# Schematic.net
KiCad netlist of a schematic drawn in Altium Designer
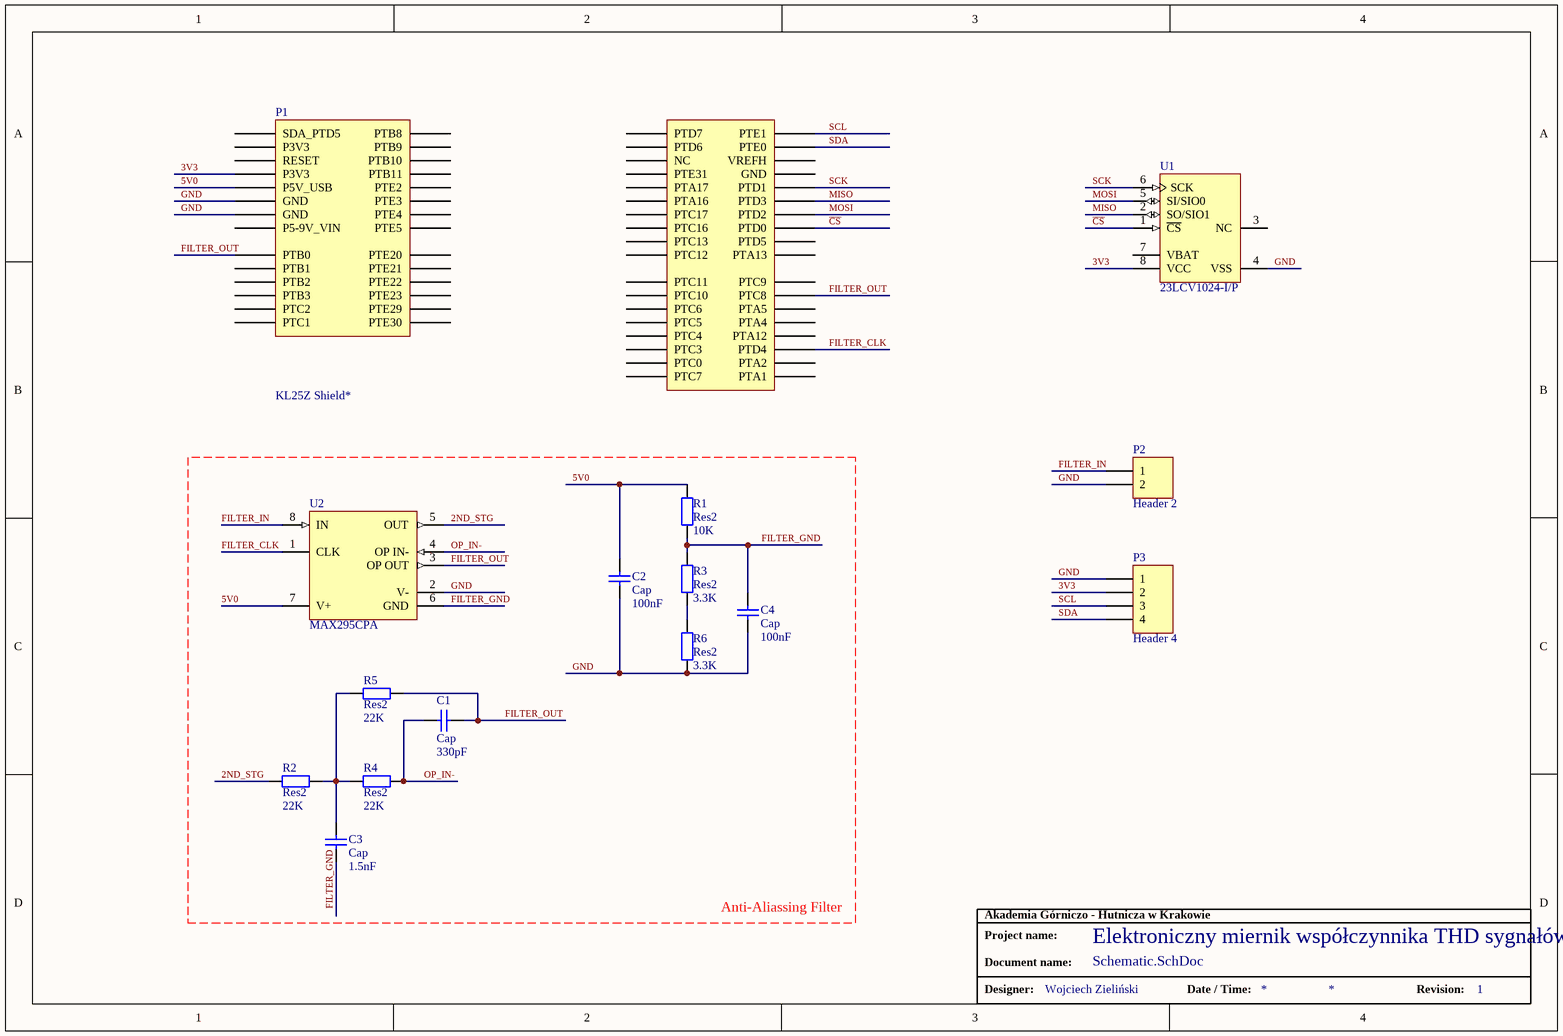
[diagram p0: Schematic.SchDoc]

(export (version "E")
  (design (tool "Eeschema 10.0.6"))
  (components
    (comp (ref "C1")
      (value "Cap")
      (footprint "RAD-0.1")
      (description "Capacitor")
      (fields (field (name "ALTIUM_VALUE") "330pF") (field (name "PUBLISHER") "Altium Limited"))
      (libsource (lib "Miscellaneous Devices") (part "Cap"))
    )
    (comp (ref "C2")
      (value "Cap")
      (footprint "RAD-0.1")
      (description "Capacitor")
      (fields (field (name "ALTIUM_VALUE") "100nF") (field (name "PUBLISHER") "Altium Limited"))
      (libsource (lib "Miscellaneous Devices") (part "Cap"))
    )
    (comp (ref "C3")
      (value "Cap")
      (footprint "RAD-0.1")
      (description "Capacitor")
      (fields (field (name "ALTIUM_VALUE") "1.5nF") (field (name "PUBLISHER") "Altium Limited"))
      (libsource (lib "Miscellaneous Devices") (part "Cap"))
    )
    (comp (ref "C4")
      (value "Cap")
      (footprint "RAD-0.1")
      (description "Capacitor")
      (fields (field (name "ALTIUM_VALUE") "100nF") (field (name "PUBLISHER") "Altium Limited"))
      (libsource (lib "Miscellaneous Devices") (part "Cap"))
    )
    (comp (ref "P1")
      (value "KL25Z Shield*")
      (footprint "Freedom KL25Z Headerarray")
      (description "FRDM KL25Z Shield")
      (libsource (lib "FreedomKL25Z") (part "Freedom KL25Z Header"))
    )
    (comp (ref "P2")
      (value "Header 2")
      (footprint "HDR1X2")
      (description "Header, 2-Pin")
      (fields (field (name "PUBLISHER") "Altium Limited"))
      (libsource (lib "Miscellaneous Connectors") (part "Header 2"))
    )
    (comp (ref "P3")
      (value "Header 4")
      (footprint "HDR1X4")
      (description "Header, 4-Pin")
      (fields (field (name "PUBLISHER") "Altium Limited"))
      (libsource (lib "Miscellaneous Connectors") (part "Header 4"))
    )
    (comp (ref "R1")
      (value "Res2")
      (footprint "AXIAL-0.4")
      (description "Resistor")
      (fields (field (name "ALTIUM_VALUE") "10K") (field (name "PUBLISHER") "Altium Limited"))
      (libsource (lib "Miscellaneous Devices") (part "Res2"))
    )
    (comp (ref "R2")
      (value "Res2")
      (footprint "AXIAL-0.4")
      (description "Resistor")
      (fields (field (name "ALTIUM_VALUE") "22K") (field (name "PUBLISHER") "Altium Limited"))
      (libsource (lib "") (part "Res2_1"))
    )
    (comp (ref "R3")
      (value "Res2")
      (footprint "AXIAL-0.4")
      (description "Resistor")
      (fields (field (name "ALTIUM_VALUE") "3.3K") (field (name "PUBLISHER") "Altium Limited"))
      (libsource (lib "Miscellaneous Devices") (part "Res2"))
    )
    (comp (ref "R4")
      (value "Res2")
      (footprint "AXIAL-0.4")
      (description "Resistor")
      (fields (field (name "ALTIUM_VALUE") "22K") (field (name "PUBLISHER") "Altium Limited"))
      (libsource (lib "") (part "Res2_1"))
    )
    (comp (ref "R5")
      (value "Res2")
      (footprint "AXIAL-0.4")
      (description "Resistor")
      (fields (field (name "ALTIUM_VALUE") "22K") (field (name "PUBLISHER") "Altium Limited"))
      (libsource (lib "") (part "Res2_1"))
    )
    (comp (ref "R6")
      (value "Res2")
      (footprint "AXIAL-0.4")
      (description "Resistor")
      (fields (field (name "ALTIUM_VALUE") "3.3K") (field (name "PUBLISHER") "Altium Limited"))
      (libsource (lib "Miscellaneous Devices") (part "Res2"))
    )
    (comp (ref "U1")
      (value "23LCV1024-I/P")
      (footprint "MCHP-PDIP-P8")
      (fields (field (name "MANUFACTURER") "Microchip"))
      (libsource (lib "Microchip Serial SRAM") (part "23LCV1024-I/P"))
    )
    (comp (ref "U2")
      (value "MAX295CPA")
      (footprint "MAXM-P8-2")
      (fields (field (name "GENERIC PART NUMBER") "MAX295"))
      (libsource (lib "Maxim Analog Filters") (part "MAX295CPA"))
    )
  )
  (nets
    (net (code "1") (name "/2ND_STG") (class "Default")
      (node (ref "R2") (pin "1") (pinfunction "1_1") (pintype "passive"))
      (node (ref "U2") (pin "5") (pinfunction "OUT_5") (pintype "output"))
    )
    (net (code "2") (name "/3V3") (class "Default")
      (node (ref "P1") (pin "7") (pinfunction "P3V3_7") (pintype "passive"))
      (node (ref "P3") (pin "2") (pinfunction "2_2") (pintype "passive"))
      (node (ref "U1") (pin "8") (pinfunction "VCC_8") (pintype "power_in"))
    )
    (net (code "3") (name "/5V0") (class "Default")
      (node (ref "C2") (pin "2") (pinfunction "2_2") (pintype "passive"))
      (node (ref "P1") (pin "9") (pinfunction "P5V_USB_9") (pintype "passive"))
      (node (ref "R1") (pin "2") (pinfunction "2_2") (pintype "passive"))
      (node (ref "U2") (pin "7") (pinfunction "V+_7") (pintype "power_in"))
    )
    (net (code "4") (name "/FILTER_CLK") (class "Default")
      (node (ref "P1") (pin "60") (pinfunction "PTD4_60") (pintype "passive"))
      (node (ref "U2") (pin "1") (pinfunction "CLK_1") (pintype "passive"))
    )
    (net (code "5") (name "/FILTER_GND") (class "Default")
      (node (ref "C3") (pin "1") (pinfunction "1_1") (pintype "passive"))
      (node (ref "C4") (pin "2") (pinfunction "2_2") (pintype "passive"))
      (node (ref "R1") (pin "1") (pinfunction "1_1") (pintype "passive"))
      (node (ref "R3") (pin "2") (pinfunction "2_2") (pintype "passive"))
      (node (ref "U2") (pin "6") (pinfunction "GND_6") (pintype "power_in"))
    )
    (net (code "6") (name "/FILTER_IN") (class "Default")
      (node (ref "P2") (pin "1") (pinfunction "1_1") (pintype "passive"))
      (node (ref "U2") (pin "8") (pinfunction "IN_8") (pintype "input"))
    )
    (net (code "7") (name "/FILTER_OUT") (class "Default")
      (node (ref "C1") (pin "2") (pinfunction "2_2") (pintype "passive"))
      (node (ref "P1") (pin "17") (pinfunction "PTB0_17") (pintype "passive"))
      (node (ref "P1") (pin "52") (pinfunction "PTC8_52") (pintype "passive"))
      (node (ref "R5") (pin "2") (pinfunction "2_2") (pintype "passive"))
      (node (ref "U2") (pin "3") (pinfunction "OP_OUT_3") (pintype "output"))
    )
    (net (code "8") (name "/GND") (class "Default")
      (node (ref "C2") (pin "1") (pinfunction "1_1") (pintype "passive"))
      (node (ref "C4") (pin "1") (pinfunction "1_1") (pintype "passive"))
      (node (ref "P1") (pin "11") (pinfunction "GND_11") (pintype "passive"))
      (node (ref "P1") (pin "13") (pinfunction "GND_13") (pintype "passive"))
      (node (ref "P2") (pin "2") (pinfunction "2_2") (pintype "passive"))
      (node (ref "P3") (pin "1") (pinfunction "1_1") (pintype "passive"))
      (node (ref "R6") (pin "1") (pinfunction "1_1") (pintype "passive"))
      (node (ref "U1") (pin "4") (pinfunction "VSS_4") (pintype "power_in"))
      (node (ref "U2") (pin "2") (pinfunction "V-_2") (pintype "power_in"))
    )
    (net (code "9") (name "/MISO") (class "Default")
      (node (ref "P1") (pin "40") (pinfunction "PTD3_40") (pintype "passive"))
      (node (ref "U1") (pin "2") (pinfunction "SO/SIO1_2") (pintype "bidirectional"))
    )
    (net (code "10") (name "/MOSI") (class "Default")
      (node (ref "P1") (pin "42") (pinfunction "PTD2_42") (pintype "passive"))
      (node (ref "U1") (pin "5") (pinfunction "SI/SIO0_5") (pintype "bidirectional"))
    )
    (net (code "11") (name "/OP_IN-") (class "Default")
      (node (ref "C1") (pin "1") (pinfunction "1_1") (pintype "passive"))
      (node (ref "R4") (pin "2") (pinfunction "2_2") (pintype "passive"))
      (node (ref "U2") (pin "4") (pinfunction "OP_IN-_4") (pintype "input"))
    )
    (net (code "12") (name "/SCK") (class "Default")
      (node (ref "P1") (pin "38") (pinfunction "PTD1_38") (pintype "passive"))
      (node (ref "U1") (pin "6") (pinfunction "SCK_6") (pintype "input"))
    )
    (net (code "13") (name "/SCL") (class "Default")
      (node (ref "P1") (pin "30") (pinfunction "PTE1_30") (pintype "passive"))
      (node (ref "P3") (pin "3") (pinfunction "3_3") (pintype "passive"))
    )
    (net (code "14") (name "/SDA") (class "Default")
      (node (ref "P1") (pin "32") (pinfunction "PTE0_32") (pintype "passive"))
      (node (ref "P3") (pin "4") (pinfunction "4_4") (pintype "passive"))
    )
    (net (code "15") (name "/~{CS}") (class "Default")
      (node (ref "P1") (pin "44") (pinfunction "PTD0_44") (pintype "passive"))
      (node (ref "U1") (pin "1") (pinfunction "~{CS}_1") (pintype "input"))
    )
    (net (code "16") (name "Net-(C3-Pad2)") (class "Default")
      (node (ref "C3") (pin "2") (pinfunction "2_2") (pintype "passive"))
      (node (ref "R2") (pin "2") (pinfunction "2_2") (pintype "passive"))
      (node (ref "R4") (pin "1") (pinfunction "1_1") (pintype "passive"))
      (node (ref "R5") (pin "1") (pinfunction "1_1") (pintype "passive"))
    )
    (net (code "17") (name "Net-(R3-Pad1)") (class "Default")
      (node (ref "R3") (pin "1") (pinfunction "1_1") (pintype "passive"))
      (node (ref "R6") (pin "2") (pinfunction "2_2") (pintype "passive"))
    )
    (net (code "18") (name "unconnected-(P1-GND-Pad36)") (class "Default")
      (node (ref "P1") (pin "36") (pinfunction "GND_36") (pintype "passive"))
    )
    (net (code "19") (name "unconnected-(P1-NC-Pad33)") (class "Default")
      (node (ref "P1") (pin "33") (pinfunction "NC_33") (pintype "passive"))
    )
    (net (code "20") (name "unconnected-(P1-P3V3-Pad3)") (class "Default")
      (node (ref "P1") (pin "3") (pinfunction "P3V3_3") (pintype "passive"))
    )
    (net (code "21") (name "unconnected-(P1-P5-9V_VIN-Pad15)") (class "Default")
      (node (ref "P1") (pin "15") (pinfunction "P5-9V_VIN_15") (pintype "passive"))
    )
    (net (code "22") (name "unconnected-(P1-PTA1-Pad64)") (class "Default")
      (node (ref "P1") (pin "64") (pinfunction "PTA1_64") (pintype "passive"))
    )
    (net (code "23") (name "unconnected-(P1-PTA2-Pad62)") (class "Default")
      (node (ref "P1") (pin "62") (pinfunction "PTA2_62") (pintype "passive"))
    )
    (net (code "24") (name "unconnected-(P1-PTA4-Pad56)") (class "Default")
      (node (ref "P1") (pin "56") (pinfunction "PTA4_56") (pintype "passive"))
    )
    (net (code "25") (name "unconnected-(P1-PTA5-Pad54)") (class "Default")
      (node (ref "P1") (pin "54") (pinfunction "PTA5_54") (pintype "passive"))
    )
    (net (code "26") (name "unconnected-(P1-PTA12-Pad58)") (class "Default")
      (node (ref "P1") (pin "58") (pinfunction "PTA12_58") (pintype "passive"))
    )
    (net (code "27") (name "unconnected-(P1-PTA13-Pad48)") (class "Default")
      (node (ref "P1") (pin "48") (pinfunction "PTA13_48") (pintype "passive"))
    )
    (net (code "28") (name "unconnected-(P1-PTA16-Pad39)") (class "Default")
      (node (ref "P1") (pin "39") (pinfunction "PTA16_39") (pintype "passive"))
    )
    (net (code "29") (name "unconnected-(P1-PTA17-Pad37)") (class "Default")
      (node (ref "P1") (pin "37") (pinfunction "PTA17_37") (pintype "passive"))
    )
    (net (code "30") (name "unconnected-(P1-PTB1-Pad19)") (class "Default")
      (node (ref "P1") (pin "19") (pinfunction "PTB1_19") (pintype "passive"))
    )
    (net (code "31") (name "unconnected-(P1-PTB2-Pad21)") (class "Default")
      (node (ref "P1") (pin "21") (pinfunction "PTB2_21") (pintype "passive"))
    )
    (net (code "32") (name "unconnected-(P1-PTB3-Pad23)") (class "Default")
      (node (ref "P1") (pin "23") (pinfunction "PTB3_23") (pintype "passive"))
    )
    (net (code "33") (name "unconnected-(P1-PTB8-Pad2)") (class "Default")
      (node (ref "P1") (pin "2") (pinfunction "PTB8_2") (pintype "passive"))
    )
    (net (code "34") (name "unconnected-(P1-PTB9-Pad4)") (class "Default")
      (node (ref "P1") (pin "4") (pinfunction "PTB9_4") (pintype "passive"))
    )
    (net (code "35") (name "unconnected-(P1-PTB10-Pad6)") (class "Default")
      (node (ref "P1") (pin "6") (pinfunction "PTB10_6") (pintype "passive"))
    )
    (net (code "36") (name "unconnected-(P1-PTB11-Pad8)") (class "Default")
      (node (ref "P1") (pin "8") (pinfunction "PTB11_8") (pintype "passive"))
    )
    (net (code "37") (name "unconnected-(P1-PTC0-Pad61)") (class "Default")
      (node (ref "P1") (pin "61") (pinfunction "PTC0_61") (pintype "passive"))
    )
    (net (code "38") (name "unconnected-(P1-PTC1-Pad27)") (class "Default")
      (node (ref "P1") (pin "27") (pinfunction "PTC1_27") (pintype "passive"))
    )
    (net (code "39") (name "unconnected-(P1-PTC2-Pad25)") (class "Default")
      (node (ref "P1") (pin "25") (pinfunction "PTC2_25") (pintype "passive"))
    )
    (net (code "40") (name "unconnected-(P1-PTC3-Pad59)") (class "Default")
      (node (ref "P1") (pin "59") (pinfunction "PTC3_59") (pintype "passive"))
    )
    (net (code "41") (name "unconnected-(P1-PTC4-Pad57)") (class "Default")
      (node (ref "P1") (pin "57") (pinfunction "PTC4_57") (pintype "passive"))
    )
    (net (code "42") (name "unconnected-(P1-PTC5-Pad55)") (class "Default")
      (node (ref "P1") (pin "55") (pinfunction "PTC5_55") (pintype "passive"))
    )
    (net (code "43") (name "unconnected-(P1-PTC6-Pad53)") (class "Default")
      (node (ref "P1") (pin "53") (pinfunction "PTC6_53") (pintype "passive"))
    )
    (net (code "44") (name "unconnected-(P1-PTC7-Pad63)") (class "Default")
      (node (ref "P1") (pin "63") (pinfunction "PTC7_63") (pintype "passive"))
    )
    (net (code "45") (name "unconnected-(P1-PTC9-Pad50)") (class "Default")
      (node (ref "P1") (pin "50") (pinfunction "PTC9_50") (pintype "passive"))
    )
    (net (code "46") (name "unconnected-(P1-PTC10-Pad51)") (class "Default")
      (node (ref "P1") (pin "51") (pinfunction "PTC10_51") (pintype "passive"))
    )
    (net (code "47") (name "unconnected-(P1-PTC11-Pad49)") (class "Default")
      (node (ref "P1") (pin "49") (pinfunction "PTC11_49") (pintype "passive"))
    )
    (net (code "48") (name "unconnected-(P1-PTC12-Pad47)") (class "Default")
      (node (ref "P1") (pin "47") (pinfunction "PTC12_47") (pintype "passive"))
    )
    (net (code "49") (name "unconnected-(P1-PTC13-Pad45)") (class "Default")
      (node (ref "P1") (pin "45") (pinfunction "PTC13_45") (pintype "passive"))
    )
    (net (code "50") (name "unconnected-(P1-PTC16-Pad43)") (class "Default")
      (node (ref "P1") (pin "43") (pinfunction "PTC16_43") (pintype "passive"))
    )
    (net (code "51") (name "unconnected-(P1-PTC17-Pad41)") (class "Default")
      (node (ref "P1") (pin "41") (pinfunction "PTC17_41") (pintype "passive"))
    )
    (net (code "52") (name "unconnected-(P1-PTD5-Pad46)") (class "Default")
      (node (ref "P1") (pin "46") (pinfunction "PTD5_46") (pintype "passive"))
    )
    (net (code "53") (name "unconnected-(P1-PTD6-Pad31)") (class "Default")
      (node (ref "P1") (pin "31") (pinfunction "PTD6_31") (pintype "passive"))
    )
    (net (code "54") (name "unconnected-(P1-PTD7-Pad29)") (class "Default")
      (node (ref "P1") (pin "29") (pinfunction "PTD7_29") (pintype "passive"))
    )
    (net (code "55") (name "unconnected-(P1-PTE2-Pad10)") (class "Default")
      (node (ref "P1") (pin "10") (pinfunction "PTE2_10") (pintype "passive"))
    )
    (net (code "56") (name "unconnected-(P1-PTE3-Pad12)") (class "Default")
      (node (ref "P1") (pin "12") (pinfunction "PTE3_12") (pintype "passive"))
    )
    (net (code "57") (name "unconnected-(P1-PTE4-Pad14)") (class "Default")
      (node (ref "P1") (pin "14") (pinfunction "PTE4_14") (pintype "passive"))
    )
    (net (code "58") (name "unconnected-(P1-PTE5-Pad16)") (class "Default")
      (node (ref "P1") (pin "16") (pinfunction "PTE5_16") (pintype "passive"))
    )
    (net (code "59") (name "unconnected-(P1-PTE20-Pad18)") (class "Default")
      (node (ref "P1") (pin "18") (pinfunction "PTE20_18") (pintype "passive"))
    )
    (net (code "60") (name "unconnected-(P1-PTE21-Pad20)") (class "Default")
      (node (ref "P1") (pin "20") (pinfunction "PTE21_20") (pintype "passive"))
    )
    (net (code "61") (name "unconnected-(P1-PTE22-Pad22)") (class "Default")
      (node (ref "P1") (pin "22") (pinfunction "PTE22_22") (pintype "passive"))
    )
    (net (code "62") (name "unconnected-(P1-PTE23-Pad24)") (class "Default")
      (node (ref "P1") (pin "24") (pinfunction "PTE23_24") (pintype "passive"))
    )
    (net (code "63") (name "unconnected-(P1-PTE29-Pad26)") (class "Default")
      (node (ref "P1") (pin "26") (pinfunction "PTE29_26") (pintype "passive"))
    )
    (net (code "64") (name "unconnected-(P1-PTE30-Pad28)") (class "Default")
      (node (ref "P1") (pin "28") (pinfunction "PTE30_28") (pintype "passive"))
    )
    (net (code "65") (name "unconnected-(P1-PTE31-Pad35)") (class "Default")
      (node (ref "P1") (pin "35") (pinfunction "PTE31_35") (pintype "passive"))
    )
    (net (code "66") (name "unconnected-(P1-RESET-Pad5)") (class "Default")
      (node (ref "P1") (pin "5") (pinfunction "RESET_5") (pintype "passive"))
    )
    (net (code "67") (name "unconnected-(P1-SDA_PTD5-Pad1)") (class "Default")
      (node (ref "P1") (pin "1") (pinfunction "SDA_PTD5_1") (pintype "passive"))
    )
    (net (code "68") (name "unconnected-(P1-VREFH-Pad34)") (class "Default")
      (node (ref "P1") (pin "34") (pinfunction "VREFH_34") (pintype "passive"))
    )
    (net (code "69") (name "unconnected-(U1-NC-Pad3)") (class "Default")
      (node (ref "U1") (pin "3") (pinfunction "NC_3") (pintype "passive"))
    )
    (net (code "70") (name "unconnected-(U1-VBAT-Pad7)") (class "Default")
      (node (ref "U1") (pin "7") (pinfunction "VBAT_7") (pintype "power_in"))
    )
  )
)
